# 7_3-axis-accelerometer.net
KiCad netlist of a schematic drawn in Altium Designer
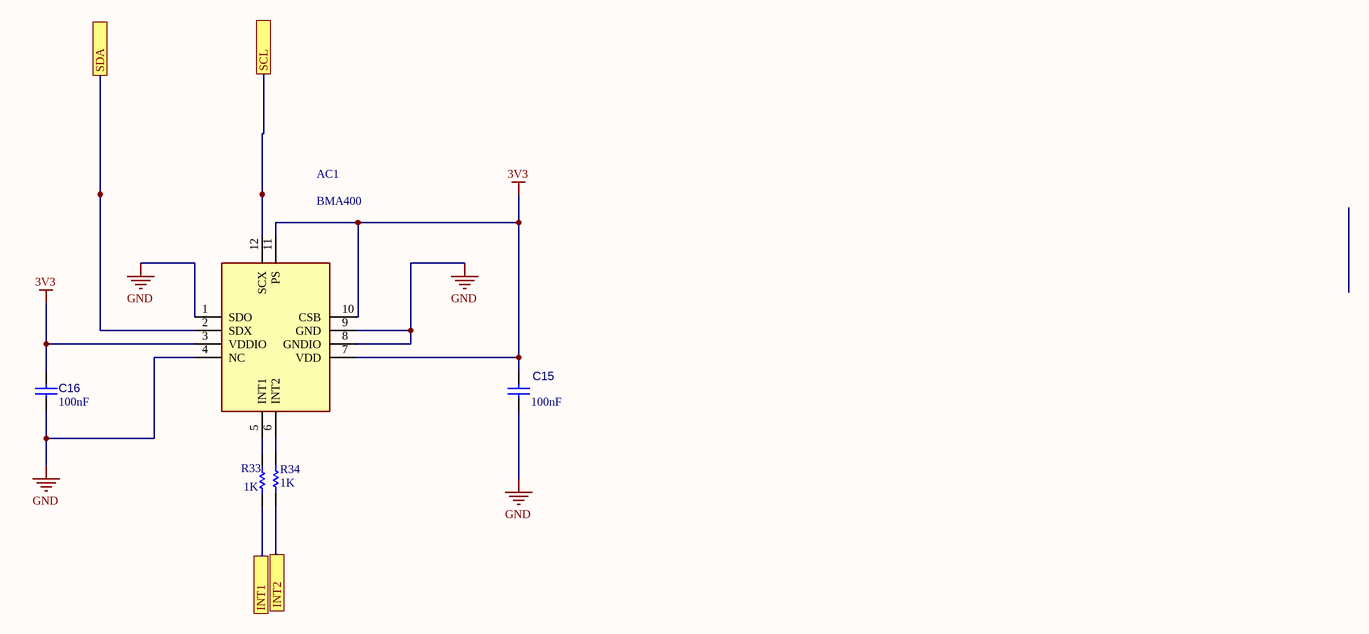
[diagram p0: [7]3-axis-accelerometer.SchDoc]

(export (version "E")
  (design (tool "Eeschema 10.0.6"))
  (components
    (comp (ref "AC1")
      (value "BMA400")
      (footprint "BMA280")
      (description "Accelerometer")
      (fields
        (field (name "MANUFACTURER_PART_NUMBER") "BMA280")
        (field (name "MOUSER PART NUMBER") "262-BMA280")
      )
      (libsource (lib "PCB_High_Voltage_Sensor") (part "BMA280"))
    )
    (comp (ref "C15")
      (value "100nF")
      (footprint "CAPC1608X90X40ML10T20")
      (description "Chip Capacitor, 100 nF, +/- 10%, 50 V, 0603 (1608 Metric)")
      (fields (field (name "TOLERANCE") "10%") (field (name "Comment") "Capacitor 100 nF +/-10% 50 V 0603"))
      (libsource (lib "Latium Technologies") (part "CAP-NP-2"))
    )
    (comp (ref "C16")
      (value "100nF")
      (footprint "CAPC1608X90X40ML10T20")
      (description "Chip Capacitor, 100 nF, +/- 10%, 50 V, 0603 (1608 Metric)")
      (fields (field (name "TOLERANCE") "10%") (field (name "Comment") "Capacitor 100 nF +/-10% 50 V 0603"))
      (libsource (lib "Latium Technologies") (part "CAP-NP-2"))
    )
    (comp (ref "R33")
      (value "1K")
      (footprint "RES 0603")
      (description "1K 1% 0.1W [0603]")
      (fields (field (name "TOLERANCE") "1%"))
      (libsource (lib "MasterLib") (part "RES 3.3M 1% 0.1W [0603]"))
    )
    (comp (ref "R34")
      (value "1K")
      (footprint "RES 0603")
      (description "1K 1% 0.1W [0603]")
      (fields (field (name "TOLERANCE") "1%"))
      (libsource (lib "MasterLib") (part "RES 3.3M 1% 0.1W [0603]"))
    )
  )
  (nets
    (net (code "1") (name "/INT1") (class "Default")
      (node (ref "R33") (pin "2") (pinfunction "2_2") (pintype "passive"))
    )
    (net (code "2") (name "/INT2") (class "Default")
      (node (ref "R34") (pin "2") (pinfunction "2_2") (pintype "passive"))
    )
    (net (code "3") (name "/SCL") (class "Default")
      (node (ref "AC1") (pin "12") (pinfunction "SCX_12") (pintype "passive"))
    )
    (net (code "4") (name "/SDA") (class "Default")
      (node (ref "AC1") (pin "2") (pinfunction "SDX_2") (pintype "passive"))
    )
    (net (code "5") (name "3V3") (class "Default")
      (node (ref "AC1") (pin "10") (pinfunction "CSB_10") (pintype "passive"))
      (node (ref "AC1") (pin "11") (pinfunction "PS_11") (pintype "passive"))
      (node (ref "AC1") (pin "3") (pinfunction "VDDIO_3") (pintype "passive"))
      (node (ref "AC1") (pin "7") (pinfunction "VDD_7") (pintype "passive"))
      (node (ref "C15") (pin "2") (pinfunction "2_2") (pintype "passive"))
      (node (ref "C16") (pin "2") (pinfunction "2_2") (pintype "passive"))
    )
    (net (code "6") (name "GND") (class "Default")
      (node (ref "AC1") (pin "1") (pinfunction "SDO_1") (pintype "passive"))
      (node (ref "AC1") (pin "4") (pinfunction "NC_4") (pintype "passive"))
      (node (ref "AC1") (pin "8") (pinfunction "GNDIO_8") (pintype "passive"))
      (node (ref "AC1") (pin "9") (pinfunction "GND_9") (pintype "passive"))
      (node (ref "C15") (pin "1") (pinfunction "1_1") (pintype "passive"))
      (node (ref "C16") (pin "1") (pinfunction "1_1") (pintype "passive"))
    )
    (net (code "7") (name "Net-(AC1-INT1)") (class "Default")
      (node (ref "AC1") (pin "5") (pinfunction "INT1_5") (pintype "passive"))
      (node (ref "R33") (pin "1") (pinfunction "1_1") (pintype "passive"))
    )
    (net (code "8") (name "Net-(AC1-INT2)") (class "Default")
      (node (ref "AC1") (pin "6") (pinfunction "INT2_6") (pintype "passive"))
      (node (ref "R34") (pin "1") (pinfunction "1_1") (pintype "passive"))
    )
  )
)
